# sla2216.net
KiCad netlist of a schematic drawn in Altium Designer
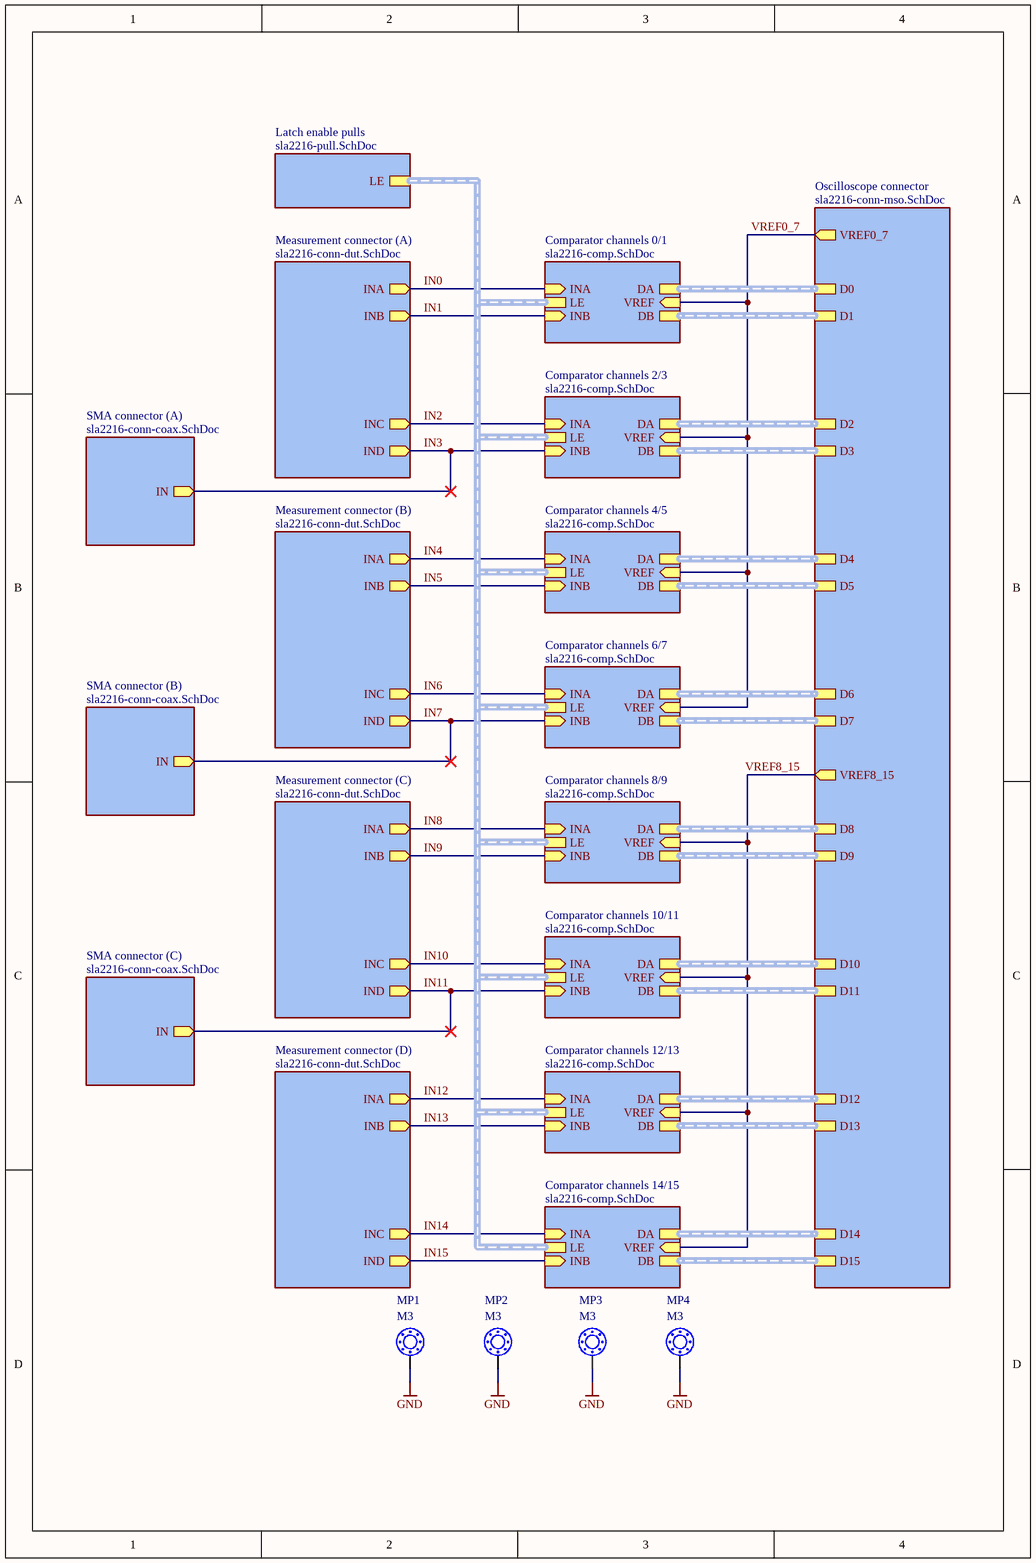
[diagram p0: sla2216.SchDoc]

(export (version "E")
  (design (tool "Eeschema 10.0.6"))
  (components
    (comp (ref "MP1")
      (value "M3")
      (footprint "MP M3")
      (description "PCB mountpoint")
      (libsource (lib "altium_lib") (part "Mountpoint"))
    )
    (comp (ref "MP2")
      (value "M3")
      (footprint "MP M3")
      (description "PCB mountpoint")
      (libsource (lib "altium_lib") (part "Mountpoint"))
    )
    (comp (ref "MP3")
      (value "M3")
      (footprint "MP M3")
      (description "PCB mountpoint")
      (libsource (lib "altium_lib") (part "Mountpoint"))
    )
    (comp (ref "MP4")
      (value "M3")
      (footprint "MP M3")
      (description "PCB mountpoint")
      (libsource (lib "altium_lib") (part "Mountpoint"))
    )
  )
  (nets
    (net (code "36") (name "GND") (class "Default")
      (node (ref "MP1") (pin "MP") (pinfunction "MP_MP") (pintype "passive"))
      (node (ref "MP2") (pin "MP") (pinfunction "MP_MP") (pintype "passive"))
      (node (ref "MP3") (pin "MP") (pinfunction "MP_MP") (pintype "passive"))
      (node (ref "MP4") (pin "MP") (pinfunction "MP_MP") (pintype "passive"))
    )
  )
)
